# USB-LPC-Programmer_modular_V3_6.net
KiCad netlist of a schematic drawn in EAGLE
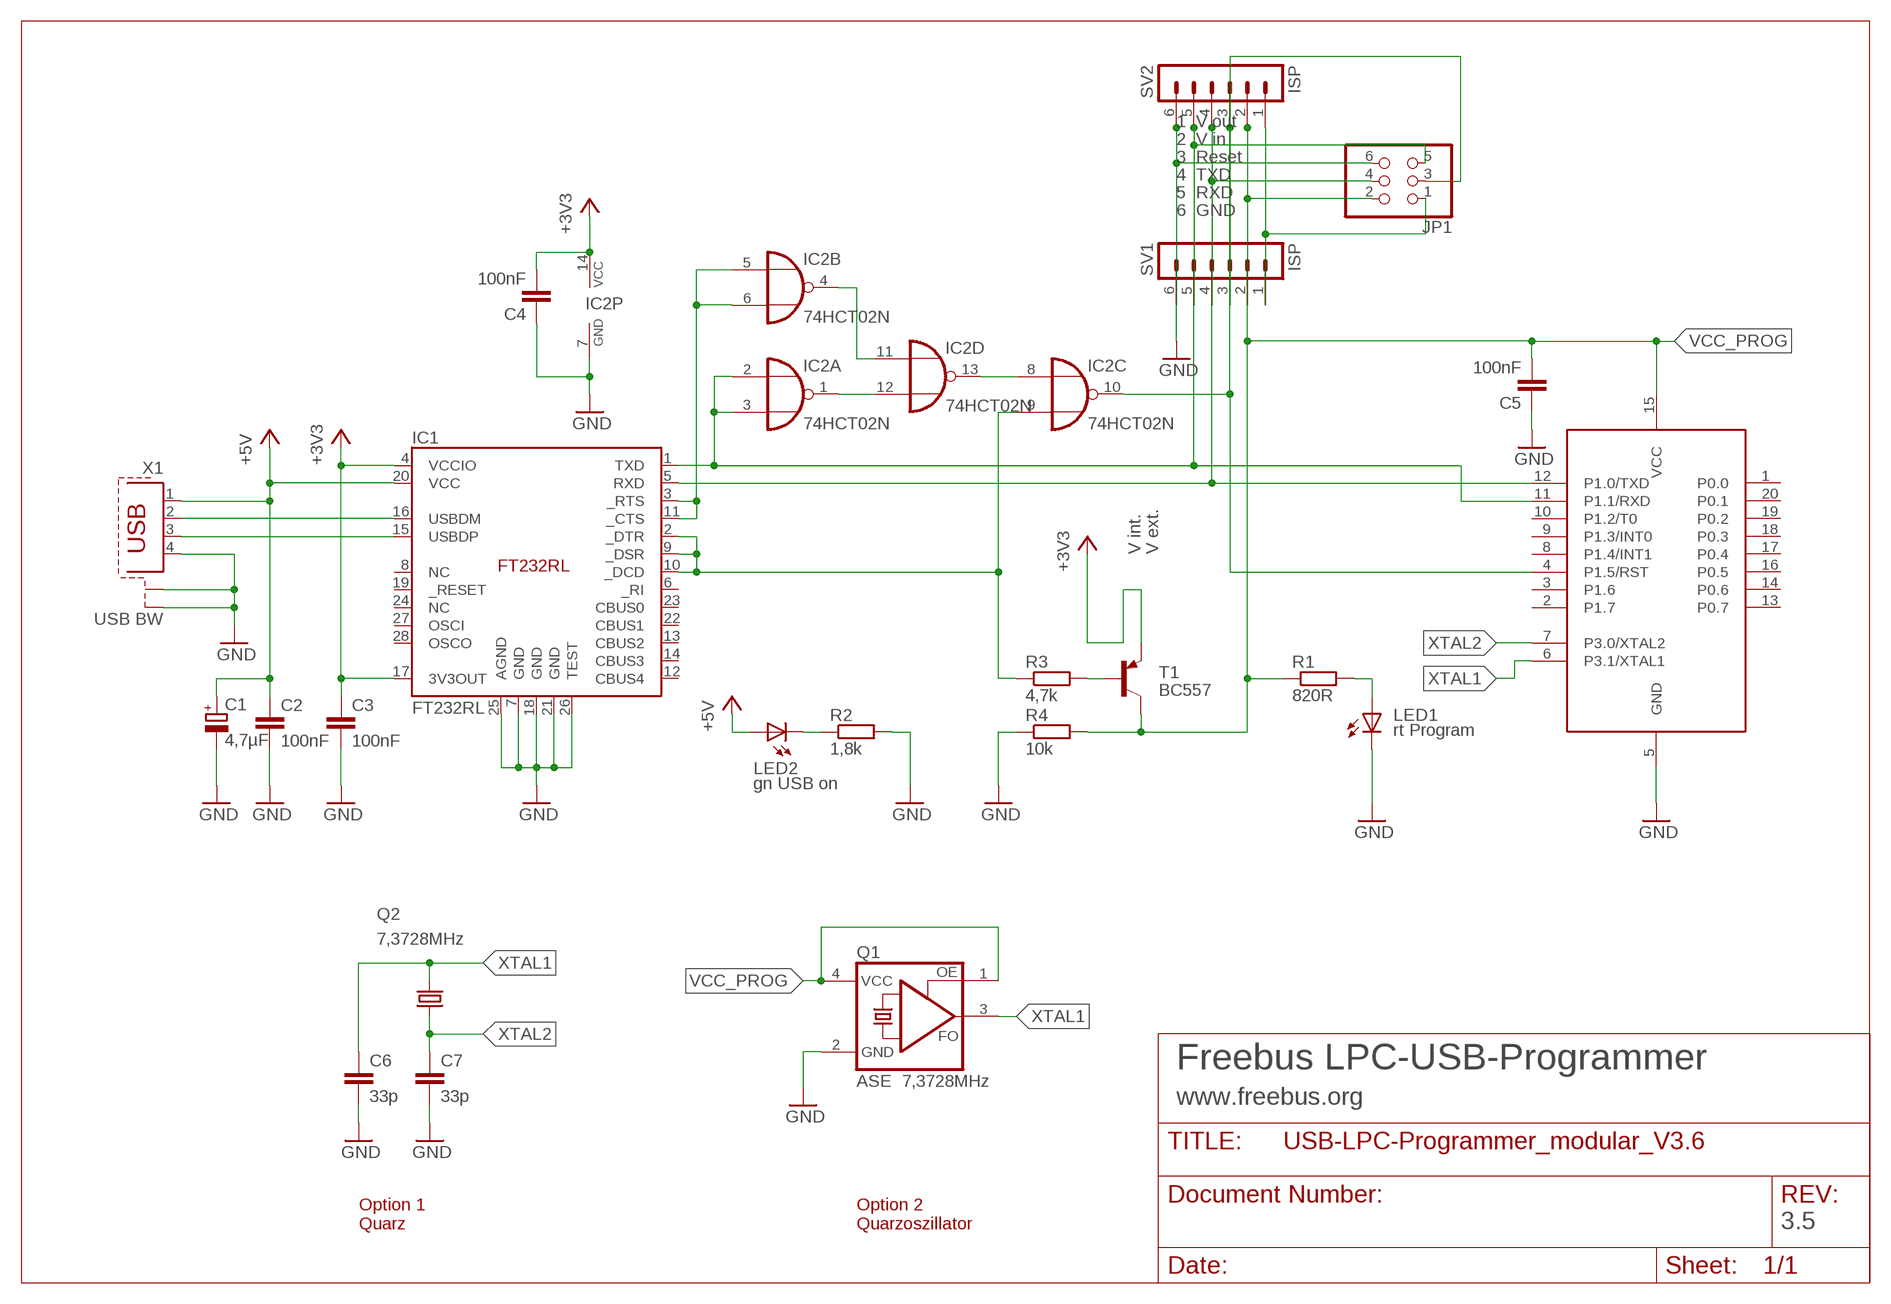
[diagram p0: schematic, sheet 1]

(export (version "E")
  (design (tool "Eeschema 10.0.6"))
  (components
    (comp (ref "89LPC922")
      (value "LPC-Sockel")
      (footprint "eagle-import:DIL20")
      (libsource (lib "eagle-import") (part "89LPC922"))
    )
    (comp (ref "C1")
      (value "4,7µF")
      (footprint "eagle-import:E2,5-6")
      (libsource (lib "eagle-import") (part "CPOL-EUE2.5-6"))
    )
    (comp (ref "C2")
      (value "100nF")
      (footprint "eagle-import:C050-024X044")
      (libsource (lib "eagle-import") (part "C-EU050-024X044"))
    )
    (comp (ref "C3")
      (value "100nF")
      (footprint "eagle-import:C050-024X044")
      (libsource (lib "eagle-import") (part "C-EU050-024X044"))
    )
    (comp (ref "C4")
      (value "100nF")
      (footprint "eagle-import:C050-024X044")
      (libsource (lib "eagle-import") (part "C-EU050-024X044"))
    )
    (comp (ref "C5")
      (value "100nF")
      (footprint "eagle-import:C050-024X044")
      (libsource (lib "eagle-import") (part "C-EU050-024X044"))
    )
    (comp (ref "C6")
      (value "33p")
      (footprint "eagle-import:C025-024X044")
      (libsource (lib "eagle-import") (part "C-EU025-024X044"))
    )
    (comp (ref "C7")
      (value "33p")
      (footprint "eagle-import:C025-024X044")
      (libsource (lib "eagle-import") (part "C-EU025-024X044"))
    )
    (comp (ref "IC1")
      (value "FT232RL")
      (footprint "eagle-import:SSOP-28")
      (libsource (lib "eagle-import") (part "FT232RL"))
    )
    (comp (ref "IC2")
      (value "74HCT02N")
      (footprint "eagle-import:DIL14")
      (libsource (lib "eagle-import") (part "7402NHCT"))
    )
    (comp (ref "JP1")
      (value "PINHD-2X3")
      (footprint "eagle-import:2X03")
      (libsource (lib "eagle-import") (part "PINHD-2X3"))
    )
    (comp (ref "LED1")
      (value "rt Program")
      (footprint "eagle-import:LED3MM")
      (libsource (lib "eagle-import") (part "LED3MM"))
    )
    (comp (ref "LED2")
      (value "gn USB on")
      (footprint "eagle-import:LED3MM")
      (libsource (lib "eagle-import") (part "LED3MM"))
    )
    (comp (ref "Q1")
      (value "ASE 7,3728MHz")
      (footprint "eagle-import:ASF")
      (libsource (lib "eagle-import") (part "ASF1"))
    )
    (comp (ref "Q2")
      (value "7,3728MHz")
      (footprint "eagle-import:HC49_S")
      (libsource (lib "eagle-import") (part "CRYSTALHC49S"))
    )
    (comp (ref "R1")
      (value "820R")
      (footprint "eagle-import:0207_7")
      (libsource (lib "eagle-import") (part "R-EU_0207/7"))
    )
    (comp (ref "R2")
      (value "1,8k")
      (footprint "eagle-import:0207_7")
      (libsource (lib "eagle-import") (part "R-EU_0207/7"))
    )
    (comp (ref "R3")
      (value "4,7k")
      (footprint "eagle-import:0204_7")
      (libsource (lib "eagle-import") (part "R-EU_0204/7"))
    )
    (comp (ref "R4")
      (value "10k")
      (footprint "eagle-import:0207_7")
      (libsource (lib "eagle-import") (part "R-EU_0207/7"))
    )
    (comp (ref "SV1")
      (value "ISP")
      (footprint "eagle-import:MA06-1")
      (libsource (lib "eagle-import") (part "MA06-1"))
    )
    (comp (ref "SV2")
      (value "ISP")
      (footprint "eagle-import:MA06-1")
      (fields (field (name "OC_FARNELL") "unknown") (field (name "OC_NEWARK") "unknown"))
      (libsource (lib "eagle-import") (part "MA06-1"))
    )
    (comp (ref "T1")
      (value "BC557")
      (footprint "eagle-import:TO92")
      (libsource (lib "eagle-import") (part "BC557"))
    )
    (comp (ref "X1")
      (value "USB BW")
      (footprint "eagle-import:PN61729-S")
      (libsource (lib "eagle-import") (part "PN61729-S"))
    )
  )
  (nets
    (net (code "1") (name "+3V3") (class "Default")
      (node (ref "C3") (pin "1") (pinfunction "1_1") (pintype "passive"))
      (node (ref "C4") (pin "2") (pinfunction "2_2") (pintype "passive"))
      (node (ref "IC1") (pin "17") (pinfunction "3V3OUT_17") (pintype "output"))
      (node (ref "IC1") (pin "4") (pinfunction "VCCIO_4") (pintype "power_in"))
      (node (ref "IC2") (pin "14") (pinfunction "VCC_14") (pintype "power_in"))
      (node (ref "T1") (pin "1") (pinfunction "E_1") (pintype "passive"))
    )
    (net (code "2") (name "+5V") (class "Default")
      (node (ref "C1") (pin "+") (pinfunction "+_+") (pintype "passive"))
      (node (ref "C2") (pin "1") (pinfunction "1_1") (pintype "passive"))
      (node (ref "IC1") (pin "20") (pinfunction "VCC_20") (pintype "power_in"))
      (node (ref "LED2") (pin "A") (pinfunction "A_A") (pintype "passive"))
      (node (ref "X1") (pin "1") (pinfunction "1_1") (pintype "passive"))
    )
    (net (code "3") (name "GND") (class "Default")
      (node (ref "89LPC922") (pin "5") (pinfunction "GND_5") (pintype "bidirectional"))
      (node (ref "C1") (pin "-") (pinfunction "-_-") (pintype "passive"))
      (node (ref "C2") (pin "2") (pinfunction "2_2") (pintype "passive"))
      (node (ref "C3") (pin "2") (pinfunction "2_2") (pintype "passive"))
      (node (ref "C4") (pin "1") (pinfunction "1_1") (pintype "passive"))
      (node (ref "C5") (pin "1") (pinfunction "1_1") (pintype "passive"))
      (node (ref "C6") (pin "2") (pinfunction "2_2") (pintype "passive"))
      (node (ref "C7") (pin "2") (pinfunction "2_2") (pintype "passive"))
      (node (ref "IC1") (pin "18") (pinfunction "GND_18") (pintype "power_in"))
      (node (ref "IC1") (pin "21") (pinfunction "GND_21") (pintype "power_in"))
      (node (ref "IC1") (pin "25") (pinfunction "AGND_25") (pintype "power_in"))
      (node (ref "IC1") (pin "26") (pinfunction "TEST_26") (pintype "bidirectional"))
      (node (ref "IC1") (pin "7") (pinfunction "GND_7") (pintype "power_in"))
      (node (ref "IC2") (pin "7") (pinfunction "GND_7") (pintype "power_in"))
      (node (ref "JP1") (pin "6") (pinfunction "6_6") (pintype "passive"))
      (node (ref "LED1") (pin "K") (pinfunction "C_K") (pintype "passive"))
      (node (ref "Q1") (pin "2") (pinfunction "GND_2") (pintype "power_in"))
      (node (ref "R2") (pin "2") (pinfunction "2_2") (pintype "passive"))
      (node (ref "R4") (pin "1") (pinfunction "1_1") (pintype "passive"))
      (node (ref "SV1") (pin "6") (pinfunction "6_6") (pintype "passive"))
      (node (ref "SV2") (pin "6") (pinfunction "6_6") (pintype "passive"))
      (node (ref "X1") (pin "4") (pinfunction "4_4") (pintype "passive"))
      (node (ref "X1") (pin "S1") (pinfunction "S1_S1") (pintype "passive"))
      (node (ref "X1") (pin "S2") (pinfunction "S2_S2") (pintype "passive"))
    )
    (net (code "4") (name "Net-(89LPC922-P1.0{slash}TXD)") (class "Default")
      (node (ref "89LPC922") (pin "12") (pinfunction "P1.0/TXD_12") (pintype "bidirectional"))
      (node (ref "IC1") (pin "5") (pinfunction "RXD_5") (pintype "input"))
      (node (ref "JP1") (pin "4") (pinfunction "4_4") (pintype "passive"))
      (node (ref "SV1") (pin "4") (pinfunction "4_4") (pintype "passive"))
      (node (ref "SV2") (pin "4") (pinfunction "4_4") (pintype "passive"))
    )
    (net (code "5") (name "Net-(89LPC922-P1.1{slash}RXD)") (class "Default")
      (node (ref "89LPC922") (pin "11") (pinfunction "P1.1/RXD_11") (pintype "bidirectional"))
      (node (ref "IC1") (pin "1") (pinfunction "TXD_1") (pintype "output"))
      (node (ref "IC2") (pin "2") (pinfunction "I0_2") (pintype "input"))
      (node (ref "IC2") (pin "3") (pinfunction "I1_3") (pintype "input"))
      (node (ref "JP1") (pin "5") (pinfunction "5_5") (pintype "passive"))
      (node (ref "SV1") (pin "5") (pinfunction "5_5") (pintype "passive"))
      (node (ref "SV2") (pin "5") (pinfunction "5_5") (pintype "passive"))
    )
    (net (code "6") (name "Net-(89LPC922-P1.5{slash}RST)") (class "Default")
      (node (ref "89LPC922") (pin "4") (pinfunction "P1.5/RST_4") (pintype "bidirectional"))
      (node (ref "IC2") (pin "10") (pinfunction "O_10") (pintype "output"))
      (node (ref "JP1") (pin "3") (pinfunction "3_3") (pintype "passive"))
      (node (ref "SV1") (pin "3") (pinfunction "3_3") (pintype "passive"))
      (node (ref "SV2") (pin "3") (pinfunction "3_3") (pintype "passive"))
    )
    (net (code "7") (name "Net-(IC1-USBDM)") (class "Default")
      (node (ref "IC1") (pin "16") (pinfunction "USBDM_16") (pintype "bidirectional"))
      (node (ref "X1") (pin "2") (pinfunction "2_2") (pintype "passive"))
    )
    (net (code "8") (name "Net-(IC1-USBDP)") (class "Default")
      (node (ref "IC1") (pin "15") (pinfunction "USBDP_15") (pintype "bidirectional"))
      (node (ref "X1") (pin "3") (pinfunction "3_3") (pintype "passive"))
    )
    (net (code "9") (name "Net-(IC1-_CTS)") (class "Default")
      (node (ref "IC1") (pin "11") (pinfunction "_CTS_11") (pintype "input"))
      (node (ref "IC1") (pin "3") (pinfunction "_RTS_3") (pintype "output"))
      (node (ref "IC2") (pin "5") (pinfunction "I0_5") (pintype "input"))
      (node (ref "IC2") (pin "6") (pinfunction "I1_6") (pintype "input"))
    )
    (net (code "10") (name "Net-(IC1-_DCD)") (class "Default")
      (node (ref "IC1") (pin "10") (pinfunction "_DCD_10") (pintype "input"))
      (node (ref "IC1") (pin "2") (pinfunction "_DTR_2") (pintype "input"))
      (node (ref "IC1") (pin "9") (pinfunction "_DSR_9") (pintype "input"))
      (node (ref "IC2") (pin "9") (pinfunction "I1_9") (pintype "input"))
      (node (ref "R3") (pin "1") (pinfunction "1_1") (pintype "passive"))
    )
    (net (code "11") (name "Net-(IC2A-O)") (class "Default")
      (node (ref "IC2") (pin "1") (pinfunction "O_1") (pintype "output"))
      (node (ref "IC2") (pin "12") (pinfunction "I1_12") (pintype "input"))
    )
    (net (code "12") (name "Net-(IC2B-O)") (class "Default")
      (node (ref "IC2") (pin "11") (pinfunction "I0_11") (pintype "input"))
      (node (ref "IC2") (pin "4") (pinfunction "O_4") (pintype "output"))
    )
    (net (code "13") (name "Net-(IC2C-I0)") (class "Default")
      (node (ref "IC2") (pin "13") (pinfunction "O_13") (pintype "output"))
      (node (ref "IC2") (pin "8") (pinfunction "I0_8") (pintype "input"))
    )
    (net (code "14") (name "Net-(JP1-Pad1)") (class "Default")
      (node (ref "JP1") (pin "1") (pinfunction "1_1") (pintype "passive"))
      (node (ref "SV1") (pin "1") (pinfunction "1_1") (pintype "passive"))
      (node (ref "SV2") (pin "1") (pinfunction "1_1") (pintype "passive"))
    )
    (net (code "15") (name "Net-(LED1-PadA)") (class "Default")
      (node (ref "LED1") (pin "A") (pinfunction "A_A") (pintype "passive"))
      (node (ref "R1") (pin "2") (pinfunction "2_2") (pintype "passive"))
    )
    (net (code "16") (name "Net-(LED2-C)") (class "Default")
      (node (ref "LED2") (pin "K") (pinfunction "C_K") (pintype "passive"))
      (node (ref "R2") (pin "1") (pinfunction "1_1") (pintype "passive"))
    )
    (net (code "17") (name "Net-(T1-B)") (class "Default")
      (node (ref "R3") (pin "2") (pinfunction "2_2") (pintype "passive"))
      (node (ref "T1") (pin "2") (pinfunction "B_2") (pintype "passive"))
    )
    (net (code "18") (name "VCC_PROG") (class "Default")
      (node (ref "89LPC922") (pin "15") (pinfunction "VCC_15") (pintype "bidirectional"))
      (node (ref "C5") (pin "2") (pinfunction "2_2") (pintype "passive"))
      (node (ref "JP1") (pin "2") (pinfunction "2_2") (pintype "passive"))
      (node (ref "Q1") (pin "1") (pinfunction "OE_1") (pintype "input"))
      (node (ref "Q1") (pin "4") (pinfunction "VCC_4") (pintype "power_in"))
      (node (ref "R1") (pin "1") (pinfunction "1_1") (pintype "passive"))
      (node (ref "R4") (pin "2") (pinfunction "2_2") (pintype "passive"))
      (node (ref "SV1") (pin "2") (pinfunction "2_2") (pintype "passive"))
      (node (ref "SV2") (pin "2") (pinfunction "2_2") (pintype "passive"))
      (node (ref "T1") (pin "3") (pinfunction "C_3") (pintype "passive"))
    )
    (net (code "19") (name "XTAL1") (class "Default")
      (node (ref "89LPC922") (pin "6") (pinfunction "P3.1/XTAL1_6") (pintype "bidirectional"))
      (node (ref "C6") (pin "1") (pinfunction "1_1") (pintype "passive"))
      (node (ref "Q1") (pin "3") (pinfunction "FO_3") (pintype "output"))
      (node (ref "Q2") (pin "2") (pinfunction "2_2") (pintype "passive"))
    )
    (net (code "20") (name "XTAL2") (class "Default")
      (node (ref "89LPC922") (pin "7") (pinfunction "P3.0/XTAL2_7") (pintype "bidirectional"))
      (node (ref "C7") (pin "1") (pinfunction "1_1") (pintype "passive"))
      (node (ref "Q2") (pin "1") (pinfunction "1_1") (pintype "passive"))
    )
    (net (code "21") (name "unconnected-(89LPC922-P0.0-Pad1)") (class "Default")
      (node (ref "89LPC922") (pin "1") (pinfunction "P0.0_1") (pintype "bidirectional"))
    )
    (net (code "22") (name "unconnected-(89LPC922-P0.1-Pad20)") (class "Default")
      (node (ref "89LPC922") (pin "20") (pinfunction "P0.1_20") (pintype "bidirectional"))
    )
    (net (code "23") (name "unconnected-(89LPC922-P0.2-Pad19)") (class "Default")
      (node (ref "89LPC922") (pin "19") (pinfunction "P0.2_19") (pintype "bidirectional"))
    )
    (net (code "24") (name "unconnected-(89LPC922-P0.3-Pad18)") (class "Default")
      (node (ref "89LPC922") (pin "18") (pinfunction "P0.3_18") (pintype "bidirectional"))
    )
    (net (code "25") (name "unconnected-(89LPC922-P0.4-Pad17)") (class "Default")
      (node (ref "89LPC922") (pin "17") (pinfunction "P0.4_17") (pintype "bidirectional"))
    )
    (net (code "26") (name "unconnected-(89LPC922-P0.5-Pad16)") (class "Default")
      (node (ref "89LPC922") (pin "16") (pinfunction "P0.5_16") (pintype "bidirectional"))
    )
    (net (code "27") (name "unconnected-(89LPC922-P0.6-Pad14)") (class "Default")
      (node (ref "89LPC922") (pin "14") (pinfunction "P0.6_14") (pintype "bidirectional"))
    )
    (net (code "28") (name "unconnected-(89LPC922-P0.7-Pad13)") (class "Default")
      (node (ref "89LPC922") (pin "13") (pinfunction "P0.7_13") (pintype "bidirectional"))
    )
    (net (code "29") (name "unconnected-(89LPC922-P1.2{slash}T0-Pad10)") (class "Default")
      (node (ref "89LPC922") (pin "10") (pinfunction "P1.2/T0_10") (pintype "bidirectional"))
    )
    (net (code "30") (name "unconnected-(89LPC922-P1.3{slash}INT0-Pad9)") (class "Default")
      (node (ref "89LPC922") (pin "9") (pinfunction "P1.3/INT0_9") (pintype "bidirectional"))
    )
    (net (code "31") (name "unconnected-(89LPC922-P1.4{slash}INT1-Pad8)") (class "Default")
      (node (ref "89LPC922") (pin "8") (pinfunction "P1.4/INT1_8") (pintype "bidirectional"))
    )
    (net (code "32") (name "unconnected-(89LPC922-P1.6-Pad3)") (class "Default")
      (node (ref "89LPC922") (pin "3") (pinfunction "P1.6_3") (pintype "bidirectional"))
    )
    (net (code "33") (name "unconnected-(89LPC922-P1.7-Pad2)") (class "Default")
      (node (ref "89LPC922") (pin "2") (pinfunction "P1.7_2") (pintype "bidirectional"))
    )
    (net (code "34") (name "unconnected-(IC1-CBUS0-Pad23)") (class "Default")
      (node (ref "IC1") (pin "23") (pinfunction "CBUS0_23") (pintype "bidirectional"))
    )
    (net (code "35") (name "unconnected-(IC1-CBUS1-Pad22)") (class "Default")
      (node (ref "IC1") (pin "22") (pinfunction "CBUS1_22") (pintype "bidirectional"))
    )
    (net (code "36") (name "unconnected-(IC1-CBUS2-Pad13)") (class "Default")
      (node (ref "IC1") (pin "13") (pinfunction "CBUS2_13") (pintype "bidirectional"))
    )
    (net (code "37") (name "unconnected-(IC1-CBUS3-Pad14)") (class "Default")
      (node (ref "IC1") (pin "14") (pinfunction "CBUS3_14") (pintype "bidirectional"))
    )
    (net (code "38") (name "unconnected-(IC1-CBUS4-Pad12)") (class "Default")
      (node (ref "IC1") (pin "12") (pinfunction "CBUS4_12") (pintype "bidirectional"))
    )
    (net (code "39") (name "unconnected-(IC1-NC-Pad8)") (class "Default")
      (node (ref "IC1") (pin "8") (pinfunction "NC_8") (pintype "no_connect"))
    )
    (net (code "40") (name "unconnected-(IC1-NC-Pad24)") (class "Default")
      (node (ref "IC1") (pin "24") (pinfunction "NC_24") (pintype "no_connect"))
    )
    (net (code "41") (name "unconnected-(IC1-OSCI-Pad27)") (class "Default")
      (node (ref "IC1") (pin "27") (pinfunction "OSCI_27") (pintype "input"))
    )
    (net (code "42") (name "unconnected-(IC1-OSCO-Pad28)") (class "Default")
      (node (ref "IC1") (pin "28") (pinfunction "OSCO_28") (pintype "output"))
    )
    (net (code "43") (name "unconnected-(IC1-_RESET-Pad19)") (class "Default")
      (node (ref "IC1") (pin "19") (pinfunction "_RESET_19") (pintype "input"))
    )
    (net (code "44") (name "unconnected-(IC1-_RI-Pad6)") (class "Default")
      (node (ref "IC1") (pin "6") (pinfunction "_RI_6") (pintype "input"))
    )
  )
)
